# 5_High_Voltage.net
KiCad netlist of a schematic drawn in Altium Designer
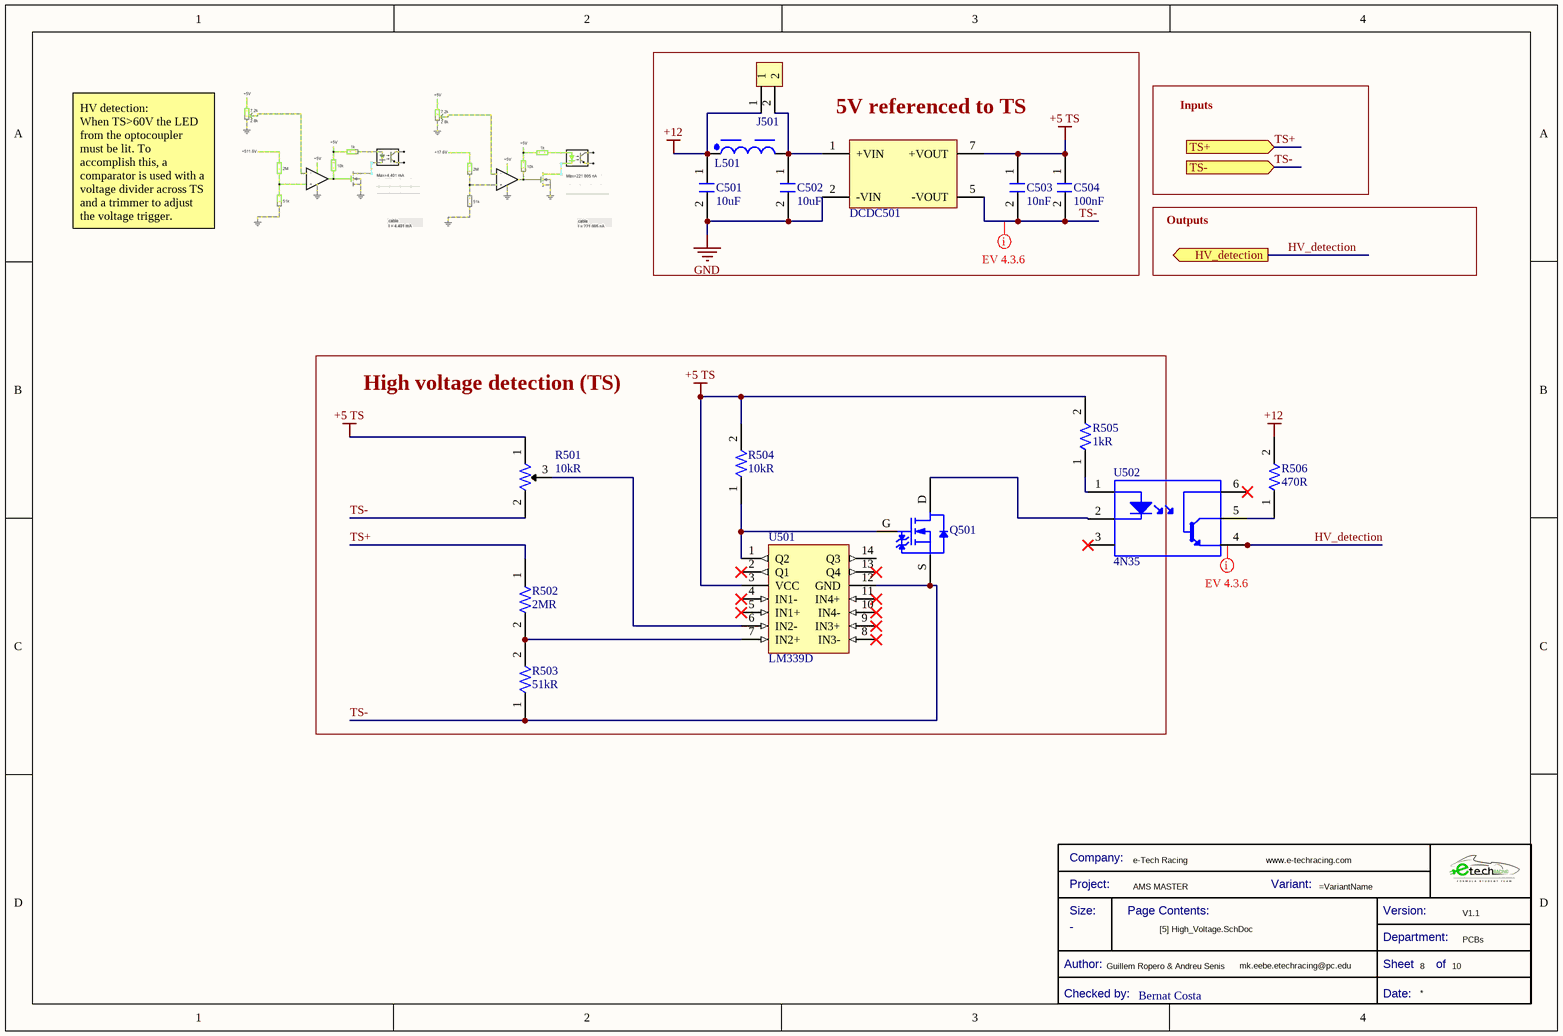
[diagram p0: [5] High_Voltage.SchDoc]

(export (version "E")
  (design (tool "Eeschema 10.0.6"))
  (components
    (comp (ref "C501")
      (value "GRJ32ER71H106KE11L")
      (footprint "C10u-50V-1210FNPMLCC-X7R")
      (description "Multilayer Ceramic Capacitors MLCC - SMD/SMT 1210 10uF 50volts X7R +/-10% Soft Term")
      (fields
        (field (name "MANUFACTURER") "Murata")
        (field (name "TOLERANCE") "10%")
        (field (name "CAPACITANCE") "10uF")
        (field (name ".CREATOR") "DR")
      )
      (libsource (lib "Passives") (part "C10u-50V-1210FNPMLCC-X7R"))
    )
    (comp (ref "C502")
      (value "GRJ32ER71H106KE11L")
      (footprint "C10u-50V-1210FNPMLCC-X7R")
      (description "Multilayer Ceramic Capacitors MLCC - SMD/SMT 1210 10uF 50volts X7R +/-10% Soft Term")
      (fields
        (field (name "MANUFACTURER") "Murata")
        (field (name "TOLERANCE") "10%")
        (field (name "CAPACITANCE") "10uF")
        (field (name ".CREATOR") "DR")
      )
      (libsource (lib "Passives") (part "C10u-50V-1210FNPMLCC-X7R"))
    )
    (comp (ref "C503")
      (value "885012207092")
      (footprint "C0805FNPC-R")
      (description "Cap, 0.01ΜF, 50V, 10%, X7R, 0805")
      (fields
        (field (name "TOLERANCE") "10%")
        (field (name "CAPACITANCE") "10nF")
        (field (name ".CREATOR") "DR")
      )
      (libsource (lib "Passives") (part "C10n-50V-0805FNPC-X7R"))
    )
    (comp (ref "C504")
      (value "885012207098")
      (footprint "C0805FNPC-R")
      (description "Cap, 0.1ΜF, 50V, 10%, X7R, 0805")
      (fields
        (field (name "TOLERANCE") "10%")
        (field (name "CAPACITANCE") "100nF")
        (field (name ".CREATOR") "DR")
      )
      (libsource (lib "Passives") (part "C100n-50V-0805FNPC-X7R"))
    )
    (comp (ref "DCDC501")
      (value "1779405241")
      (footprint "DCDC2W-ISO/1779405X41")
      (description "WPME-FISM Fixed Isolated Module, SIP-7, 10.8-13.2Vin, 5Vout")
      (fields (field (name "MANUFACTURER") "Wurth Elektronik"))
      (libsource (lib "Semiconductor") (part "DCDC-ISO-2W/12V/5V"))
    )
    (comp (ref "J501")
      (value "61300211121")
      (footprint "J_Pinheader_1x2")
      (description "CONN HEADER 2 POS 2.54")
      (fields (field (name "MANUFACTURER") "Molex") (field (name ".CREATOR") "GP"))
      (libsource (lib "Electromechanical") (part "J_Jumper"))
    )
    (comp (ref "L501")
      (value "744042470")
      (footprint "L_Power_ 47uH")
      (description "WE-TPC SMT Tiny Power Inductor, size 4818, 47uH, 0.62A, 540mOhm")
      (fields (field (name "MANUFACTURER") "Wurth Elektronik"))
      (libsource (lib "Passives") (part "L_47uH_0.6A"))
    )
    (comp (ref "Q501")
      (value "SQ2318BES-T1_GE3")
      (footprint "TRT-NCH-3/35-CPH")
      (description "Automotive N-channel 40 V (d-s) 175C Mosfet SOT-23")
      (fields (field (name ".CREATOR") "DO"))
      (libsource (lib "Semiconductor") (part "TRT-NCH-8/40-SQ"))
    )
    (comp (ref "R501")
      (value "3296W-1-103LF")
      (footprint "R10k-VTR")
      (description "Trimmer, Cermet, Rest 10 Kilohms, PCB, 25 Turns, Pwr-Rtg 0.5W, 3296 Series")
      (fields
        (field (name "MANUFACTURER") "Bourns")
        (field (name "TOLERANCE") "10%")
        (field (name "RESISTANCE") "10kR")
        (field (name ".CREATOR") "DO")
      )
      (libsource (lib "Passives") (part "R10k-VTR"))
    )
    (comp (ref "R502")
      (value "R2M-2512FTK")
      (footprint "R2512FTK")
      (description "Current Sense Resistors - SMD 3watts .002ohms 1%")
      (fields
        (field (name "MANUFACTURER") "Vishay Dale")
        (field (name "MANUFACTURER PART NUMBER") "WSLP25122L000FEA")
        (field (name "RESISTANCE") "2MR")
      )
      (libsource (lib "Passives") (part "R2M-2512FTK"))
    )
    (comp (ref "R503")
      (value "CRCW120610K0FKEA")
      (footprint "R1206FTK-W")
      (description "Res Thick Film 1206 51K Ohm 1% 1/4W ±100ppm/°C Molded SMD SMD Punched Carrier T/R")
      (fields
        (field (name "MANUFACTURER") "Panasonic")
        (field (name "MANUFACTURER PART NUMBER") "ERJ-S08F5102V")
        (field (name "RESISTANCE") "51kR")
        (field (name ".CREATOR") "DO")
      )
      (libsource (lib "Passives") (part "R51k-1206FTK"))
    )
    (comp (ref "R504")
      (value "CR0805-JW-103ELF")
      (footprint "R0805FTK")
      (fields
        (field (name "TOLERANCE") "5%")
        (field (name "RESISTANCE") "10kR")
        (field (name ".CREATOR") "DR")
      )
      (libsource (lib "Passives") (part "R10k-0805FTK"))
    )
    (comp (ref "R505")
      (value "CR0805-JW-102ELF")
      (footprint "R0805FTK")
      (description "Res Thick Film 0805 1K Ohm 5% 1/8W ±200ppm/°C Molded SMD SMD Paper Tape on Plastic Reel")
      (fields
        (field (name "TOLERANCE") "5%")
        (field (name "RESISTANCE") "1kR")
        (field (name ".CREATOR") "GP")
      )
      (libsource (lib "Passives") (part "R1k-0805FTK"))
    )
    (comp (ref "R506")
      (value "CR0805-FX-4700GLF")
      (footprint "R0805FTK")
      (description "Res Thick Film 0805 470 Ohm 1% 1/8W ±100ppm/°C Molded SMD SMD Paper Tape on Plastic Reel")
      (fields
        (field (name "TOLERANCE") "1%")
        (field (name "RESISTANCE") "470R")
        (field (name ".CREATOR") "DR")
      )
      (libsource (lib "Passives") (part "R470-0805FTK"))
    )
    (comp (ref "U501")
      (value "LM339D")
      (footprint "Array_4_Amp_LM339D")
      (description "Comparator Quad ±18V/36V 14-Pin SOIC Tube")
      (fields
        (field (name "MANUFACTURER") "Texas Instruments")
        (field (name "MANUFACTURER PART NUMBER") "LM339D")
        (field (name ".CREATOR") "DO")
      )
      (libsource (lib "Integrated circuits") (part "Array_4_Amp_LM339D"))
    )
    (comp (ref "U502")
      (value "4N35")
      (footprint "Optocoupler_4N35")
      (description "Optocoupler DC-IN 1-CH Transistor With Base DC-OUT 6-Pin PDIP SMD T/R")
      (fields
        (field (name "MANUFACTURER") "Vishay Lite-On")
        (field (name "MANUFACTURER PART NUMBER") "CNY17-4S-TA1")
        (field (name ".CREATOR") "DO")
      )
      (libsource (lib "Semiconductor") (part "Optocoupler_4N35"))
    )
  )
  (nets
    (net (code "1") (name "+5 TS") (class "Default")
      (node (ref "C503") (pin "1") (pinfunction "1_1") (pintype "passive"))
      (node (ref "C504") (pin "1") (pinfunction "1_1") (pintype "passive"))
      (node (ref "DCDC501") (pin "7") (pinfunction "+VOUT_7") (pintype "passive"))
      (node (ref "R501") (pin "1") (pinfunction "2_1") (pintype "passive"))
      (node (ref "R504") (pin "2") (pinfunction "2_2") (pintype "passive"))
      (node (ref "R505") (pin "2") (pinfunction "2_2") (pintype "passive"))
      (node (ref "U501") (pin "3") (pinfunction "VCC_3") (pintype "power_in"))
    )
    (net (code "2") (name "+12") (class "Default")
      (node (ref "C501") (pin "1") (pinfunction "1_1") (pintype "passive"))
      (node (ref "J501") (pin "1") (pinfunction "1_1") (pintype "passive"))
      (node (ref "L501") (pin "1") (pinfunction "1_1") (pintype "passive"))
      (node (ref "R506") (pin "2") (pinfunction "2_2") (pintype "passive"))
    )
    (net (code "3") (name "/HV_detection") (class "Default")
      (node (ref "U502") (pin "4") (pinfunction "E_4") (pintype "passive"))
    )
    (net (code "4") (name "/TS+") (class "Default")
      (node (ref "R502") (pin "1") (pinfunction "1_1") (pintype "passive"))
    )
    (net (code "5") (name "/TS-") (class "Default")
      (node (ref "C503") (pin "2") (pinfunction "2_2") (pintype "passive"))
      (node (ref "C504") (pin "2") (pinfunction "2_2") (pintype "passive"))
      (node (ref "DCDC501") (pin "5") (pinfunction "-VOUT_5") (pintype "passive"))
      (node (ref "Q501") (pin "S") (pinfunction "S_S") (pintype "passive"))
      (node (ref "R501") (pin "2") (pinfunction "2_2") (pintype "passive"))
      (node (ref "R503") (pin "1") (pinfunction "1_1") (pintype "passive"))
      (node (ref "U501") (pin "12") (pinfunction "GND_12") (pintype "power_in"))
    )
    (net (code "6") (name "GND") (class "Default")
      (node (ref "C501") (pin "2") (pinfunction "2_2") (pintype "passive"))
      (node (ref "C502") (pin "2") (pinfunction "2_2") (pintype "passive"))
      (node (ref "DCDC501") (pin "2") (pinfunction "-VIN_2") (pintype "passive"))
    )
    (net (code "7") (name "Net-(DCDC501-+VIN)") (class "Default")
      (node (ref "C502") (pin "1") (pinfunction "1_1") (pintype "passive"))
      (node (ref "DCDC501") (pin "1") (pinfunction "+VIN_1") (pintype "passive"))
      (node (ref "J501") (pin "2") (pinfunction "2_2") (pintype "passive"))
      (node (ref "L501") (pin "2") (pinfunction "2_2") (pintype "passive"))
    )
    (net (code "8") (name "Net-(R506-Pad1)") (class "Default")
      (node (ref "R506") (pin "1") (pinfunction "1_1") (pintype "passive"))
      (node (ref "U502") (pin "5") (pinfunction "E_5") (pintype "passive"))
    )
    (net (code "9") (name "Net-(U501-IN2+)") (class "Default")
      (node (ref "R502") (pin "2") (pinfunction "2_2") (pintype "passive"))
      (node (ref "R503") (pin "2") (pinfunction "2_2") (pintype "passive"))
      (node (ref "U501") (pin "7") (pinfunction "IN2+_7") (pintype "input"))
    )
    (net (code "10") (name "Net-(U501-IN2-)") (class "Default")
      (node (ref "R501") (pin "3") (pinfunction "3_3") (pintype "passive"))
      (node (ref "U501") (pin "6") (pinfunction "IN2-_6") (pintype "input"))
    )
    (net (code "11") (name "Net-(U501-Q2)") (class "Default")
      (node (ref "Q501") (pin "G") (pinfunction "G_G") (pintype "passive"))
      (node (ref "R504") (pin "1") (pinfunction "1_1") (pintype "passive"))
      (node (ref "U501") (pin "1") (pinfunction "Q2_1") (pintype "output"))
    )
    (net (code "12") (name "Net-(U502-A)") (class "Default")
      (node (ref "R505") (pin "1") (pinfunction "1_1") (pintype "passive"))
      (node (ref "U502") (pin "1") (pinfunction "A_1") (pintype "passive"))
    )
    (net (code "13") (name "Net-(U502-K)") (class "Default")
      (node (ref "Q501") (pin "D") (pinfunction "D_D") (pintype "passive"))
      (node (ref "U502") (pin "2") (pinfunction "K_2") (pintype "passive"))
    )
    (net (code "14") (name "unconnected-(U501-IN1+-Pad5)") (class "Default")
      (node (ref "U501") (pin "5") (pinfunction "IN1+_5") (pintype "input+no_connect"))
    )
    (net (code "15") (name "unconnected-(U501-IN1--Pad4)") (class "Default")
      (node (ref "U501") (pin "4") (pinfunction "IN1-_4") (pintype "input+no_connect"))
    )
    (net (code "16") (name "unconnected-(U501-IN3+-Pad9)") (class "Default")
      (node (ref "U501") (pin "9") (pinfunction "IN3+_9") (pintype "input+no_connect"))
    )
    (net (code "17") (name "unconnected-(U501-IN3--Pad8)") (class "Default")
      (node (ref "U501") (pin "8") (pinfunction "IN3-_8") (pintype "input+no_connect"))
    )
    (net (code "18") (name "unconnected-(U501-IN4+-Pad11)") (class "Default")
      (node (ref "U501") (pin "11") (pinfunction "IN4+_11") (pintype "input+no_connect"))
    )
    (net (code "19") (name "unconnected-(U501-IN4--Pad10)") (class "Default")
      (node (ref "U501") (pin "10") (pinfunction "IN4-_10") (pintype "input+no_connect"))
    )
    (net (code "20") (name "unconnected-(U501-Q1-Pad2)") (class "Default")
      (node (ref "U501") (pin "2") (pinfunction "Q1_2") (pintype "output+no_connect"))
    )
    (net (code "21") (name "unconnected-(U501-Q3-Pad14)") (class "Default")
      (node (ref "U501") (pin "14") (pinfunction "Q3_14") (pintype "output"))
    )
    (net (code "22") (name "unconnected-(U501-Q4-Pad13)") (class "Default")
      (node (ref "U501") (pin "13") (pinfunction "Q4_13") (pintype "output+no_connect"))
    )
    (net (code "23") (name "unconnected-(U502-C-Pad3)") (class "Default")
      (node (ref "U502") (pin "3") (pinfunction "C_3") (pintype "passive+no_connect"))
    )
    (net (code "24") (name "unconnected-(U502-E-Pad6)") (class "Default")
      (node (ref "U502") (pin "6") (pinfunction "E_6") (pintype "passive+no_connect"))
    )
  )
)
